# 9v_BOOST_CONVERTERS.net
KiCad netlist of a schematic drawn in Altium Designer
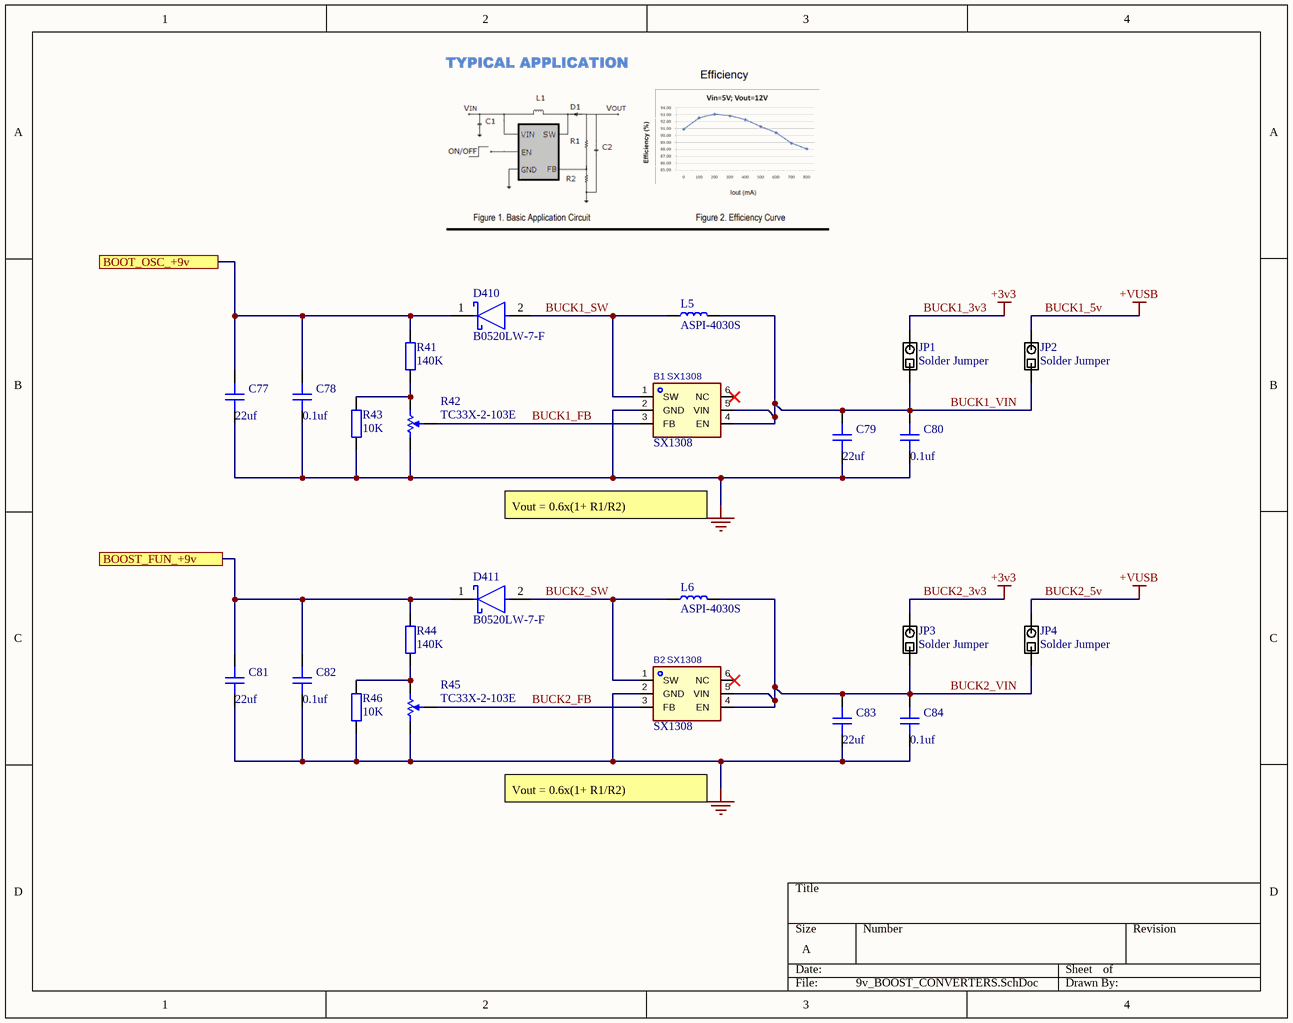
[diagram p0: 9v_BOOST_CONVERTERS.SchDoc]

(export (version "E")
  (design (tool "Eeschema 10.0.6"))
  (components
    (comp (ref "B1")
      (value "SX1308")
      (footprint "SOT-23-6_L2.9-W1.6-P0.95-LS2.8-BL")
      (fields (field (name "LCSC PART") "C78162") (field (name "ALTIUM_VALUE") "SX1308"))
      (libsource (lib "sx1308") (part "SX1308"))
    )
    (comp (ref "B2")
      (value "SX1308")
      (footprint "SOT-23-6_L2.9-W1.6-P0.95-LS2.8-BL")
      (fields (field (name "LCSC PART") "C78162") (field (name "ALTIUM_VALUE") "SX1308"))
      (libsource (lib "sx1308") (part "SX1308"))
    )
    (comp (ref "C77")
      (value "22uf")
      (footprint "CAP_0603")
      (description "Capacitor SMD 0603")
      (libsource (lib "Schematic-Lib-PhilsLab") (part "CAP_0603"))
    )
    (comp (ref "C78")
      (value "0.1uf")
      (footprint "CAP_0603")
      (description "Capacitor SMD 0603")
      (libsource (lib "Schematic-Lib-PhilsLab") (part "CAP_0603"))
    )
    (comp (ref "C79")
      (value "22uf")
      (footprint "CAP_0603")
      (description "Capacitor SMD 0603")
      (libsource (lib "Schematic-Lib-PhilsLab") (part "CAP_0603"))
    )
    (comp (ref "C80")
      (value "0.1uf")
      (footprint "CAP_0603")
      (description "Capacitor SMD 0603")
      (libsource (lib "Schematic-Lib-PhilsLab") (part "CAP_0603"))
    )
    (comp (ref "C81")
      (value "22uf")
      (footprint "CAP_0603")
      (description "Capacitor SMD 0603")
      (libsource (lib "Schematic-Lib-PhilsLab") (part "CAP_0603"))
    )
    (comp (ref "C82")
      (value "0.1uf")
      (footprint "CAP_0603")
      (description "Capacitor SMD 0603")
      (libsource (lib "Schematic-Lib-PhilsLab") (part "CAP_0603"))
    )
    (comp (ref "C83")
      (value "22uf")
      (footprint "CAP_0603")
      (description "Capacitor SMD 0603")
      (libsource (lib "Schematic-Lib-PhilsLab") (part "CAP_0603"))
    )
    (comp (ref "C84")
      (value "0.1uf")
      (footprint "CAP_0603")
      (description "Capacitor SMD 0603")
      (libsource (lib "Schematic-Lib-PhilsLab") (part "CAP_0603"))
    )
    (comp (ref "D410")
      (value "B0520LW-7-F")
      (footprint "FP-SOD123-MFG")
      (description "DIODE SCHOTTKY 20V 500MA SOD123")
      (fields
        (field (name "OCTOPART") "https://octopart.com/b0520lw-7-f-diodes+inc.-325707")
        (field (name "MANUFACTURER") "Diodes Inc.")
      )
      (libsource (lib "Altium Content Vault") (part "1d6ec82d83fb6aee721767c19dac4b9"))
    )
    (comp (ref "D411")
      (value "B0520LW-7-F")
      (footprint "FP-SOD123-MFG")
      (description "DIODE SCHOTTKY 20V 500MA SOD123")
      (fields
        (field (name "OCTOPART") "https://octopart.com/b0520lw-7-f-diodes+inc.-325707")
        (field (name "MANUFACTURER") "Diodes Inc.")
      )
      (libsource (lib "Altium Content Vault") (part "1d6ec82d83fb6aee721767c19dac4b9"))
    )
    (comp (ref "JP1")
      (value "Solder Jumper")
      (footprint "SolderJumper_Single")
      (description "Solder Jumper Single 0.5mm Pitch")
      (libsource (lib "Schematic-Lib-PhilsLab") (part "SolderJumper_Single"))
    )
    (comp (ref "JP2")
      (value "Solder Jumper")
      (footprint "SolderJumper_Single")
      (description "Solder Jumper Single 0.5mm Pitch")
      (libsource (lib "Schematic-Lib-PhilsLab") (part "SolderJumper_Single"))
    )
    (comp (ref "JP3")
      (value "Solder Jumper")
      (footprint "SolderJumper_Single")
      (description "Solder Jumper Single 0.5mm Pitch")
      (libsource (lib "Schematic-Lib-PhilsLab") (part "SolderJumper_Single"))
    )
    (comp (ref "JP4")
      (value "Solder Jumper")
      (footprint "SolderJumper_Single")
      (description "Solder Jumper Single 0.5mm Pitch")
      (libsource (lib "Schematic-Lib-PhilsLab") (part "SolderJumper_Single"))
    )
    (comp (ref "L5")
      (value "ASPI-4030S")
      (footprint "ASPI-4030S")
      (description "Power Inductor SMD ASPI-4030S Series")
      (fields (field (name "MANUFACTURER") "ABRACON") (field (name "MANUFACTURER PART NUMBER") "ASPI-4030S*"))
      (libsource (lib "Schematic-Lib-PhilsLab") (part "ASPI-4030S"))
    )
    (comp (ref "L6")
      (value "ASPI-4030S")
      (footprint "ASPI-4030S")
      (description "Power Inductor SMD ASPI-4030S Series")
      (fields (field (name "MANUFACTURER") "ABRACON") (field (name "MANUFACTURER PART NUMBER") "ASPI-4030S*"))
      (libsource (lib "Schematic-Lib-PhilsLab") (part "ASPI-4030S"))
    )
    (comp (ref "R41")
      (value "140K")
      (footprint "RES_0603")
      (description "Resistor SMD 0603")
      (libsource (lib "Schematic-Lib-PhilsLab") (part "RES_0603"))
    )
    (comp (ref "R42")
      (value "TC33X-2-103E")
      (footprint "BOUR-TC33X-2_V")
      (description "Trimming Potentiometer, 10000 Ohm, -40 to 100 degC, 3-Pin SMD, RoHS, Tape and Reel")
      (fields (field (name "TOLERANCE") "25%") (field (name "MANUFACTURER") "Bourns"))
      (libsource (lib "Altium Content Vault") (part "RES-ADJ-3_A"))
    )
    (comp (ref "R43")
      (value "10K")
      (footprint "RES_0603")
      (description "Resistor SMD 0603")
      (libsource (lib "Schematic-Lib-PhilsLab") (part "RES_0603"))
    )
    (comp (ref "R44")
      (value "140K")
      (footprint "RES_0603")
      (description "Resistor SMD 0603")
      (libsource (lib "Schematic-Lib-PhilsLab") (part "RES_0603"))
    )
    (comp (ref "R45")
      (value "TC33X-2-103E")
      (footprint "BOUR-TC33X-2_V")
      (description "Trimming Potentiometer, 10000 Ohm, -40 to 100 degC, 3-Pin SMD, RoHS, Tape and Reel")
      (fields (field (name "TOLERANCE") "25%") (field (name "MANUFACTURER") "Bourns"))
      (libsource (lib "Altium Content Vault") (part "RES-ADJ-3_A"))
    )
    (comp (ref "R46")
      (value "10K")
      (footprint "RES_0603")
      (description "Resistor SMD 0603")
      (libsource (lib "Schematic-Lib-PhilsLab") (part "RES_0603"))
    )
  )
  (nets
    (net (code "1") (name "+3v3") (class "Default")
      (node (ref "JP1") (pin "2") (pinfunction "2_2") (pintype "passive"))
      (node (ref "JP3") (pin "2") (pinfunction "2_2") (pintype "passive"))
    )
    (net (code "2") (name "+VUSB") (class "Default")
      (node (ref "JP2") (pin "2") (pinfunction "2_2") (pintype "passive"))
      (node (ref "JP4") (pin "2") (pinfunction "2_2") (pintype "passive"))
    )
    (net (code "3") (name "/BOOST_FUN_+9v") (class "Default")
      (node (ref "C81") (pin "2") (pinfunction "2_2") (pintype "passive"))
      (node (ref "C82") (pin "2") (pinfunction "2_2") (pintype "passive"))
      (node (ref "D411") (pin "1") (pinfunction "C_1") (pintype "passive"))
      (node (ref "R44") (pin "2") (pinfunction "2_2") (pintype "passive"))
    )
    (net (code "4") (name "/BOOT_OSC_+9v") (class "Default")
      (node (ref "C77") (pin "2") (pinfunction "2_2") (pintype "passive"))
      (node (ref "C78") (pin "2") (pinfunction "2_2") (pintype "passive"))
      (node (ref "D410") (pin "1") (pinfunction "C_1") (pintype "passive"))
      (node (ref "R41") (pin "2") (pinfunction "2_2") (pintype "passive"))
    )
    (net (code "5") (name "/BUCK1_FB") (class "Default")
      (node (ref "B1") (pin "3") (pinfunction "FB_3") (pintype "passive"))
      (node (ref "R42") (pin "2") (pinfunction "2_2") (pintype "passive"))
    )
    (net (code "6") (name "/BUCK1_SW") (class "Default")
      (node (ref "B1") (pin "1") (pinfunction "SW_1") (pintype "passive"))
      (node (ref "D410") (pin "2") (pinfunction "A_2") (pintype "passive"))
      (node (ref "L5") (pin "1") (pinfunction "1_1") (pintype "passive"))
    )
    (net (code "7") (name "/BUCK1_VIN") (class "Default")
      (node (ref "B1") (pin "4") (pinfunction "EN_4") (pintype "passive"))
      (node (ref "B1") (pin "5") (pinfunction "VIN_5") (pintype "passive"))
      (node (ref "C79") (pin "2") (pinfunction "2_2") (pintype "passive"))
      (node (ref "C80") (pin "2") (pinfunction "2_2") (pintype "passive"))
      (node (ref "JP1") (pin "1") (pinfunction "1_1") (pintype "passive"))
      (node (ref "JP2") (pin "1") (pinfunction "1_1") (pintype "passive"))
      (node (ref "L5") (pin "2") (pinfunction "2_2") (pintype "passive"))
    )
    (net (code "8") (name "/BUCK2_FB") (class "Default")
      (node (ref "B2") (pin "3") (pinfunction "FB_3") (pintype "passive"))
      (node (ref "R45") (pin "2") (pinfunction "2_2") (pintype "passive"))
    )
    (net (code "9") (name "/BUCK2_SW") (class "Default")
      (node (ref "B2") (pin "1") (pinfunction "SW_1") (pintype "passive"))
      (node (ref "D411") (pin "2") (pinfunction "A_2") (pintype "passive"))
      (node (ref "L6") (pin "1") (pinfunction "1_1") (pintype "passive"))
    )
    (net (code "10") (name "/BUCK2_VIN") (class "Default")
      (node (ref "B2") (pin "4") (pinfunction "EN_4") (pintype "passive"))
      (node (ref "B2") (pin "5") (pinfunction "VIN_5") (pintype "passive"))
      (node (ref "C83") (pin "2") (pinfunction "2_2") (pintype "passive"))
      (node (ref "C84") (pin "2") (pinfunction "2_2") (pintype "passive"))
      (node (ref "JP3") (pin "1") (pinfunction "1_1") (pintype "passive"))
      (node (ref "JP4") (pin "1") (pinfunction "1_1") (pintype "passive"))
      (node (ref "L6") (pin "2") (pinfunction "2_2") (pintype "passive"))
    )
    (net (code "11") (name "GND") (class "Default")
      (node (ref "B1") (pin "2") (pinfunction "GND_2") (pintype "passive"))
      (node (ref "B2") (pin "2") (pinfunction "GND_2") (pintype "passive"))
      (node (ref "C77") (pin "1") (pinfunction "1_1") (pintype "passive"))
      (node (ref "C78") (pin "1") (pinfunction "1_1") (pintype "passive"))
      (node (ref "C79") (pin "1") (pinfunction "1_1") (pintype "passive"))
      (node (ref "C80") (pin "1") (pinfunction "1_1") (pintype "passive"))
      (node (ref "C81") (pin "1") (pinfunction "1_1") (pintype "passive"))
      (node (ref "C82") (pin "1") (pinfunction "1_1") (pintype "passive"))
      (node (ref "C83") (pin "1") (pinfunction "1_1") (pintype "passive"))
      (node (ref "C84") (pin "1") (pinfunction "1_1") (pintype "passive"))
      (node (ref "R42") (pin "1") (pinfunction "1_1") (pintype "passive"))
      (node (ref "R43") (pin "1") (pinfunction "1_1") (pintype "passive"))
      (node (ref "R45") (pin "1") (pinfunction "1_1") (pintype "passive"))
      (node (ref "R46") (pin "1") (pinfunction "1_1") (pintype "passive"))
    )
    (net (code "12") (name "Net-(R41-Pad1)") (class "Default")
      (node (ref "R41") (pin "1") (pinfunction "1_1") (pintype "passive"))
      (node (ref "R42") (pin "3") (pinfunction "3_3") (pintype "passive"))
      (node (ref "R43") (pin "2") (pinfunction "2_2") (pintype "passive"))
    )
    (net (code "13") (name "Net-(R44-Pad1)") (class "Default")
      (node (ref "R44") (pin "1") (pinfunction "1_1") (pintype "passive"))
      (node (ref "R45") (pin "3") (pinfunction "3_3") (pintype "passive"))
      (node (ref "R46") (pin "2") (pinfunction "2_2") (pintype "passive"))
    )
    (net (code "14") (name "unconnected-(B1-NC-Pad6)") (class "Default")
      (node (ref "B1") (pin "6") (pinfunction "NC_6") (pintype "passive+no_connect"))
    )
    (net (code "15") (name "unconnected-(B2-NC-Pad6)") (class "Default")
      (node (ref "B2") (pin "6") (pinfunction "NC_6") (pintype "passive+no_connect"))
    )
  )
)
